# ArtixBank15.net
KiCad netlist of a schematic drawn in Altium Designer
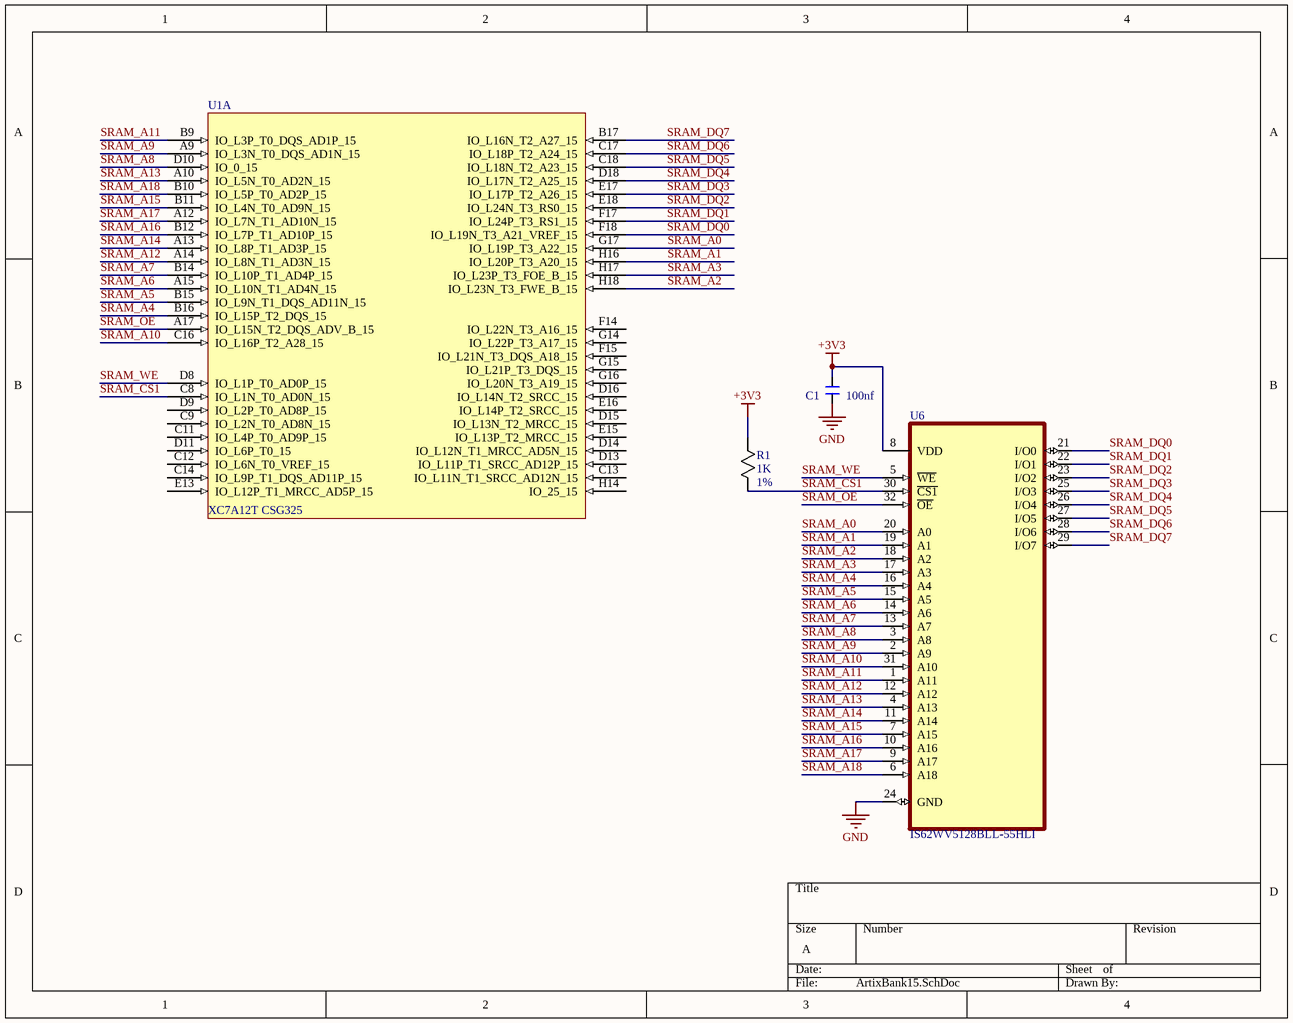
[diagram p0: ArtixBank15.SchDoc]

(export (version "E")
  (design (tool "Eeschema 10.0.6"))
  (components
    (comp (ref "C1")
      (value "100nf")
      (footprint "0402Footprint")
      (description "0402")
      (libsource (lib "Capacitors") (part "100nf_0402"))
    )
    (comp (ref "R1")
      (value "1K")
      (footprint "RES_CRCW_0402")
      (description "0402")
      (fields (field (name "TOLERANCE") "1%"))
      (libsource (lib "Resistors") (part "1k_0402"))
    )
    (comp (ref "U1")
      (value "XC7A12T CSG325")
      (footprint "BGA324C80P18X18_1500X1500X150")
      (libsource (lib "XC7A12T_1CPG238I") (part "XC7A12T_1CSG325I"))
    )
    (comp (ref "U6")
      (value "IS62WV5128BLL-55HLI")
      (footprint "SOIC50P1340X125-32N")
      (description "SRAM - Asynchronous Memory IC 4Mb _512K x 8_ Parallel 55ns 32-sTSOP I")
      (fields
        (field (name "MF") "ISSI, Integrated")
        (field (name "DIGI-KEY_PART_NUMBER") "IS62WV5128BLL-55HLI-TR-ND")
      )
      (libsource (lib "IS62WV5128BLL-55HLI") (part "IS62WV5128BLL-55HLI"))
    )
  )
  (nets
    (net (code "1") (name "+3V3") (class "Default")
      (node (ref "C1") (pin "1") (pinfunction "1_1") (pintype "passive"))
      (node (ref "R1") (pin "1") (pinfunction "1_1") (pintype "passive"))
      (node (ref "U6") (pin "8") (pinfunction "VDD_8") (pintype "power_in"))
    )
    (net (code "2") (name "/SRAM_A0") (class "Default")
      (node (ref "U1") (pin "G17") (pinfunction "IO_L19P_T3_A22_15_G17") (pintype "input"))
      (node (ref "U6") (pin "20") (pinfunction "A0_20") (pintype "input"))
    )
    (net (code "3") (name "/SRAM_A1") (class "Default")
      (node (ref "U1") (pin "H16") (pinfunction "IO_L20P_T3_A20_15_H16") (pintype "input"))
      (node (ref "U6") (pin "19") (pinfunction "A1_19") (pintype "input"))
    )
    (net (code "4") (name "/SRAM_A2") (class "Default")
      (node (ref "U1") (pin "H18") (pinfunction "IO_L23N_T3_FWE_B_15_H18") (pintype "input"))
      (node (ref "U6") (pin "18") (pinfunction "A2_18") (pintype "input"))
    )
    (net (code "5") (name "/SRAM_A3") (class "Default")
      (node (ref "U1") (pin "H17") (pinfunction "IO_L23P_T3_FOE_B_15_H17") (pintype "input"))
      (node (ref "U6") (pin "17") (pinfunction "A3_17") (pintype "input"))
    )
    (net (code "6") (name "/SRAM_A4") (class "Default")
      (node (ref "U1") (pin "B16") (pinfunction "IO_L15P_T2_DQS_15_B16") (pintype "input"))
      (node (ref "U6") (pin "16") (pinfunction "A4_16") (pintype "input"))
    )
    (net (code "7") (name "/SRAM_A5") (class "Default")
      (node (ref "U1") (pin "B15") (pinfunction "IO_L9N_T1_DQS_AD11N_15_B15") (pintype "input"))
      (node (ref "U6") (pin "15") (pinfunction "A5_15") (pintype "input"))
    )
    (net (code "8") (name "/SRAM_A6") (class "Default")
      (node (ref "U1") (pin "A15") (pinfunction "IO_L10N_T1_AD4N_15_A15") (pintype "input"))
      (node (ref "U6") (pin "14") (pinfunction "A6_14") (pintype "input"))
    )
    (net (code "9") (name "/SRAM_A7") (class "Default")
      (node (ref "U1") (pin "B14") (pinfunction "IO_L10P_T1_AD4P_15_B14") (pintype "input"))
      (node (ref "U6") (pin "13") (pinfunction "A7_13") (pintype "input"))
    )
    (net (code "10") (name "/SRAM_A8") (class "Default")
      (node (ref "U1") (pin "D10") (pinfunction "IO_0_15_D10") (pintype "input"))
      (node (ref "U6") (pin "3") (pinfunction "A8_3") (pintype "input"))
    )
    (net (code "11") (name "/SRAM_A9") (class "Default")
      (node (ref "U1") (pin "A9") (pinfunction "IO_L3N_T0_DQS_AD1N_15_A9") (pintype "input"))
      (node (ref "U6") (pin "2") (pinfunction "A9_2") (pintype "input"))
    )
    (net (code "12") (name "/SRAM_A10") (class "Default")
      (node (ref "U1") (pin "C16") (pinfunction "IO_L16P_T2_A28_15_C16") (pintype "input"))
      (node (ref "U6") (pin "31") (pinfunction "A10_31") (pintype "input"))
    )
    (net (code "13") (name "/SRAM_A11") (class "Default")
      (node (ref "U1") (pin "B9") (pinfunction "IO_L3P_T0_DQS_AD1P_15_B9") (pintype "input"))
      (node (ref "U6") (pin "1") (pinfunction "A11_1") (pintype "input"))
    )
    (net (code "14") (name "/SRAM_A12") (class "Default")
      (node (ref "U1") (pin "A14") (pinfunction "IO_L8N_T1_AD3N_15_A14") (pintype "input"))
      (node (ref "U6") (pin "12") (pinfunction "A12_12") (pintype "input"))
    )
    (net (code "15") (name "/SRAM_A13") (class "Default")
      (node (ref "U1") (pin "A10") (pinfunction "IO_L5N_T0_AD2N_15_A10") (pintype "input"))
      (node (ref "U6") (pin "4") (pinfunction "A13_4") (pintype "input"))
    )
    (net (code "16") (name "/SRAM_A14") (class "Default")
      (node (ref "U1") (pin "A13") (pinfunction "IO_L8P_T1_AD3P_15_A13") (pintype "input"))
      (node (ref "U6") (pin "11") (pinfunction "A14_11") (pintype "input"))
    )
    (net (code "17") (name "/SRAM_A15") (class "Default")
      (node (ref "U1") (pin "B11") (pinfunction "IO_L4N_T0_AD9N_15_B11") (pintype "input"))
      (node (ref "U6") (pin "7") (pinfunction "A15_7") (pintype "input"))
    )
    (net (code "18") (name "/SRAM_A16") (class "Default")
      (node (ref "U1") (pin "B12") (pinfunction "IO_L7P_T1_AD10P_15_B12") (pintype "input"))
      (node (ref "U6") (pin "10") (pinfunction "A16_10") (pintype "input"))
    )
    (net (code "19") (name "/SRAM_A17") (class "Default")
      (node (ref "U1") (pin "A12") (pinfunction "IO_L7N_T1_AD10N_15_A12") (pintype "input"))
      (node (ref "U6") (pin "9") (pinfunction "A17_9") (pintype "input"))
    )
    (net (code "20") (name "/SRAM_A18") (class "Default")
      (node (ref "U1") (pin "B10") (pinfunction "IO_L5P_T0_AD2P_15_B10") (pintype "input"))
      (node (ref "U6") (pin "6") (pinfunction "A18_6") (pintype "input"))
    )
    (net (code "21") (name "/SRAM_DQ0") (class "Default")
      (node (ref "U1") (pin "F18") (pinfunction "IO_L19N_T3_A21_VREF_15_F18") (pintype "input"))
      (node (ref "U6") (pin "21") (pinfunction "I/O0_21") (pintype "bidirectional"))
    )
    (net (code "22") (name "/SRAM_DQ1") (class "Default")
      (node (ref "U1") (pin "F17") (pinfunction "IO_L24P_T3_RS1_15_F17") (pintype "input"))
      (node (ref "U6") (pin "22") (pinfunction "I/O1_22") (pintype "bidirectional"))
    )
    (net (code "23") (name "/SRAM_DQ2") (class "Default")
      (node (ref "U1") (pin "E18") (pinfunction "IO_L24N_T3_RS0_15_E18") (pintype "input"))
      (node (ref "U6") (pin "23") (pinfunction "I/O2_23") (pintype "bidirectional"))
    )
    (net (code "24") (name "/SRAM_DQ3") (class "Default")
      (node (ref "U1") (pin "E17") (pinfunction "IO_L17P_T2_A26_15_E17") (pintype "input"))
      (node (ref "U6") (pin "25") (pinfunction "I/O3_25") (pintype "bidirectional"))
    )
    (net (code "25") (name "/SRAM_DQ4") (class "Default")
      (node (ref "U1") (pin "D18") (pinfunction "IO_L17N_T2_A25_15_D18") (pintype "input"))
      (node (ref "U6") (pin "26") (pinfunction "I/O4_26") (pintype "bidirectional"))
    )
    (net (code "26") (name "/SRAM_DQ5") (class "Default")
      (node (ref "U1") (pin "C18") (pinfunction "IO_L18N_T2_A23_15_C18") (pintype "input"))
      (node (ref "U6") (pin "27") (pinfunction "I/O5_27") (pintype "bidirectional"))
    )
    (net (code "27") (name "/SRAM_DQ6") (class "Default")
      (node (ref "U1") (pin "C17") (pinfunction "IO_L18P_T2_A24_15_C17") (pintype "input"))
      (node (ref "U6") (pin "28") (pinfunction "I/O6_28") (pintype "bidirectional"))
    )
    (net (code "28") (name "/SRAM_DQ7") (class "Default")
      (node (ref "U1") (pin "B17") (pinfunction "IO_L16N_T2_A27_15_B17") (pintype "input"))
      (node (ref "U6") (pin "29") (pinfunction "I/O7_29") (pintype "bidirectional"))
    )
    (net (code "29") (name "/SRAM_OE") (class "Default")
      (node (ref "U1") (pin "A17") (pinfunction "IO_L15N_T2_DQS_ADV_B_15_A17") (pintype "input"))
      (node (ref "U6") (pin "32") (pinfunction "~{OE}_32") (pintype "input"))
    )
    (net (code "30") (name "/SRAM_WE") (class "Default")
      (node (ref "U1") (pin "D8") (pinfunction "IO_L1P_T0_AD0P_15_D8") (pintype "input"))
      (node (ref "U6") (pin "5") (pinfunction "~{WE}_5") (pintype "input"))
    )
    (net (code "31") (name "/SRAM_~{CS1}") (class "Default")
      (node (ref "R1") (pin "2") (pinfunction "2_2") (pintype "passive"))
      (node (ref "U1") (pin "C8") (pinfunction "IO_L1N_T0_AD0N_15_C8") (pintype "input"))
      (node (ref "U6") (pin "30") (pinfunction "~{CS1}_30") (pintype "input"))
    )
    (net (code "32") (name "GND") (class "Default")
      (node (ref "C1") (pin "2") (pinfunction "2_2") (pintype "passive"))
      (node (ref "U6") (pin "24") (pinfunction "GND_24") (pintype "bidirectional"))
    )
    (net (code "33") (name "unconnected-(U1A-IO_25_15-PadH14)") (class "Default")
      (node (ref "U1") (pin "H14") (pinfunction "IO_25_15_H14") (pintype "input"))
    )
    (net (code "34") (name "unconnected-(U1A-IO_L2N_T0_AD8N_15-PadC9)") (class "Default")
      (node (ref "U1") (pin "C9") (pinfunction "IO_L2N_T0_AD8N_15_C9") (pintype "input"))
    )
    (net (code "35") (name "unconnected-(U1A-IO_L2P_T0_AD8P_15-PadD9)") (class "Default")
      (node (ref "U1") (pin "D9") (pinfunction "IO_L2P_T0_AD8P_15_D9") (pintype "input"))
    )
    (net (code "36") (name "unconnected-(U1A-IO_L4P_T0_AD9P_15-PadC11)") (class "Default")
      (node (ref "U1") (pin "C11") (pinfunction "IO_L4P_T0_AD9P_15_C11") (pintype "input"))
    )
    (net (code "37") (name "unconnected-(U1A-IO_L6N_T0_VREF_15-PadC12)") (class "Default")
      (node (ref "U1") (pin "C12") (pinfunction "IO_L6N_T0_VREF_15_C12") (pintype "input"))
    )
    (net (code "38") (name "unconnected-(U1A-IO_L6P_T0_15-PadD11)") (class "Default")
      (node (ref "U1") (pin "D11") (pinfunction "IO_L6P_T0_15_D11") (pintype "input"))
    )
    (net (code "39") (name "unconnected-(U1A-IO_L9P_T1_DQS_AD11P_15-PadC14)") (class "Default")
      (node (ref "U1") (pin "C14") (pinfunction "IO_L9P_T1_DQS_AD11P_15_C14") (pintype "input"))
    )
    (net (code "40") (name "unconnected-(U1A-IO_L11N_T1_SRCC_AD12N_15-PadC13)") (class "Default")
      (node (ref "U1") (pin "C13") (pinfunction "IO_L11N_T1_SRCC_AD12N_15_C13") (pintype "input"))
    )
    (net (code "41") (name "unconnected-(U1A-IO_L11P_T1_SRCC_AD12P_15-PadD13)") (class "Default")
      (node (ref "U1") (pin "D13") (pinfunction "IO_L11P_T1_SRCC_AD12P_15_D13") (pintype "input"))
    )
    (net (code "42") (name "unconnected-(U1A-IO_L12N_T1_MRCC_AD5N_15-PadD14)") (class "Default")
      (node (ref "U1") (pin "D14") (pinfunction "IO_L12N_T1_MRCC_AD5N_15_D14") (pintype "input"))
    )
    (net (code "43") (name "unconnected-(U1A-IO_L12P_T1_MRCC_AD5P_15-PadE13)") (class "Default")
      (node (ref "U1") (pin "E13") (pinfunction "IO_L12P_T1_MRCC_AD5P_15_E13") (pintype "input"))
    )
    (net (code "44") (name "unconnected-(U1A-IO_L13N_T2_MRCC_15-PadD15)") (class "Default")
      (node (ref "U1") (pin "D15") (pinfunction "IO_L13N_T2_MRCC_15_D15") (pintype "input"))
    )
    (net (code "45") (name "unconnected-(U1A-IO_L13P_T2_MRCC_15-PadE15)") (class "Default")
      (node (ref "U1") (pin "E15") (pinfunction "IO_L13P_T2_MRCC_15_E15") (pintype "input"))
    )
    (net (code "46") (name "unconnected-(U1A-IO_L14N_T2_SRCC_15-PadD16)") (class "Default")
      (node (ref "U1") (pin "D16") (pinfunction "IO_L14N_T2_SRCC_15_D16") (pintype "input"))
    )
    (net (code "47") (name "unconnected-(U1A-IO_L14P_T2_SRCC_15-PadE16)") (class "Default")
      (node (ref "U1") (pin "E16") (pinfunction "IO_L14P_T2_SRCC_15_E16") (pintype "input"))
    )
    (net (code "48") (name "unconnected-(U1A-IO_L20N_T3_A19_15-PadG16)") (class "Default")
      (node (ref "U1") (pin "G16") (pinfunction "IO_L20N_T3_A19_15_G16") (pintype "input"))
    )
    (net (code "49") (name "unconnected-(U1A-IO_L21N_T3_DQS_A18_15-PadF15)") (class "Default")
      (node (ref "U1") (pin "F15") (pinfunction "IO_L21N_T3_DQS_A18_15_F15") (pintype "input"))
    )
    (net (code "50") (name "unconnected-(U1A-IO_L21P_T3_DQS_15-PadG15)") (class "Default")
      (node (ref "U1") (pin "G15") (pinfunction "IO_L21P_T3_DQS_15_G15") (pintype "input"))
    )
    (net (code "51") (name "unconnected-(U1A-IO_L22N_T3_A16_15-PadF14)") (class "Default")
      (node (ref "U1") (pin "F14") (pinfunction "IO_L22N_T3_A16_15_F14") (pintype "input"))
    )
    (net (code "52") (name "unconnected-(U1A-IO_L22P_T3_A17_15-PadG14)") (class "Default")
      (node (ref "U1") (pin "G14") (pinfunction "IO_L22P_T3_A17_15_G14") (pintype "input"))
    )
  )
)
